# hlw8012_test_board.net
KiCad netlist of a schematic drawn in EAGLE
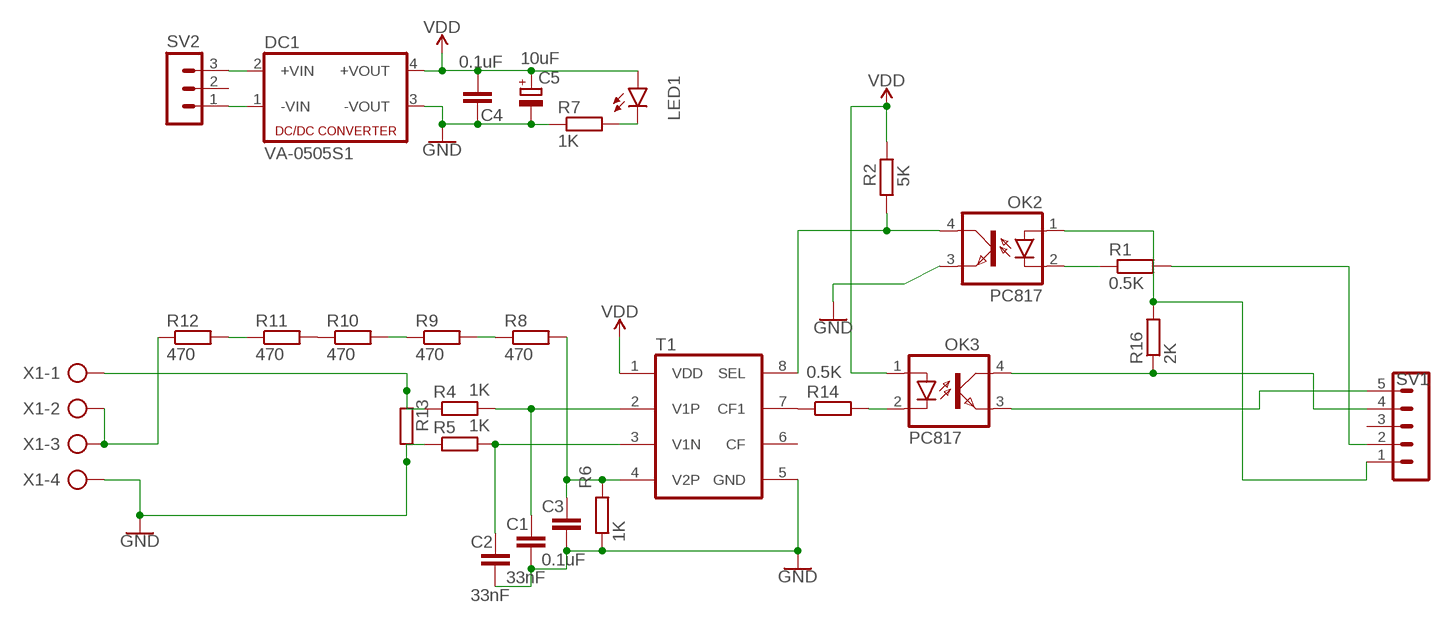
[diagram p0: schematic, sheet 1]

(export (version "E")
  (design (tool "Eeschema 10.0.6"))
  (components
    (comp (ref "C1")
      (value "33nF")
      (footprint "eagle-import:C0805")
      (libsource (lib "eagle-import") (part "C-EUC0805"))
    )
    (comp (ref "C2")
      (value "33nF")
      (footprint "eagle-import:C0805")
      (libsource (lib "eagle-import") (part "C-EUC0805"))
    )
    (comp (ref "C3")
      (value "0.1uF")
      (footprint "eagle-import:C0805")
      (libsource (lib "eagle-import") (part "C-EUC0805"))
    )
    (comp (ref "C4")
      (value "0.1uF")
      (footprint "eagle-import:C0805")
      (libsource (lib "eagle-import") (part "C-EUC0805"))
    )
    (comp (ref "C5")
      (value "10uF")
      (footprint "eagle-import:153CLV-0405")
      (libsource (lib "eagle-import") (part "CPOL-EU153CLV-0405"))
    )
    (comp (ref "DC1")
      (value "VA-0505S1")
      (footprint "eagle-import:4SIL")
      (libsource (lib "eagle-import") (part "VA-?S10505"))
    )
    (comp (ref "LED1")
      (value "LED3MM")
      (footprint "eagle-import:LED3MM")
      (libsource (lib "eagle-import") (part "LED3MM"))
    )
    (comp (ref "OK2")
      (value "PC817")
      (footprint "eagle-import:DIL04")
      (fields (field (name "MPN") "PC817X4J000F"))
      (libsource (lib "eagle-import") (part "PC817"))
    )
    (comp (ref "OK3")
      (value "PC817")
      (footprint "eagle-import:DIL04")
      (fields (field (name "MPN") "PC817X4J000F"))
      (libsource (lib "eagle-import") (part "PC817"))
    )
    (comp (ref "R1")
      (value "0.5K")
      (footprint "eagle-import:M0805")
      (libsource (lib "eagle-import") (part "R-EU_M0805"))
    )
    (comp (ref "R2")
      (value "5K")
      (footprint "eagle-import:M0805")
      (libsource (lib "eagle-import") (part "R-EU_M0805"))
    )
    (comp (ref "R4")
      (value "1K")
      (footprint "eagle-import:M0805")
      (libsource (lib "eagle-import") (part "R-EU_M0805"))
    )
    (comp (ref "R5")
      (value "1K")
      (footprint "eagle-import:M0805")
      (libsource (lib "eagle-import") (part "R-EU_M0805"))
    )
    (comp (ref "R6")
      (value "1K")
      (footprint "eagle-import:M0805")
      (libsource (lib "eagle-import") (part "R-EU_M0805"))
    )
    (comp (ref "R7")
      (value "1K")
      (footprint "eagle-import:M0805")
      (libsource (lib "eagle-import") (part "R-EU_M0805"))
    )
    (comp (ref "R8")
      (value "470")
      (footprint "eagle-import:M0805")
      (libsource (lib "eagle-import") (part "R-EU_M0805"))
    )
    (comp (ref "R9")
      (value "470")
      (footprint "eagle-import:M0805")
      (libsource (lib "eagle-import") (part "R-EU_M0805"))
    )
    (comp (ref "R10")
      (value "470")
      (footprint "eagle-import:M0805")
      (libsource (lib "eagle-import") (part "R-EU_M0805"))
    )
    (comp (ref "R11")
      (value "470")
      (footprint "eagle-import:M0805")
      (libsource (lib "eagle-import") (part "R-EU_M0805"))
    )
    (comp (ref "R12")
      (value "470")
      (footprint "eagle-import:M0805")
      (libsource (lib "eagle-import") (part "R-EU_M0805"))
    )
    (comp (ref "R13")
      (value "PMD")
      (footprint "eagle-import:PMD")
      (libsource (lib "eagle-import") (part "PMD"))
    )
    (comp (ref "R14")
      (value "0.5K")
      (footprint "eagle-import:M0805")
      (libsource (lib "eagle-import") (part "R-EU_M0805"))
    )
    (comp (ref "R16")
      (value "2K")
      (footprint "eagle-import:M0805")
      (libsource (lib "eagle-import") (part "R-EU_M0805"))
    )
    (comp (ref "SV1")
      (value "MA05-1")
      (footprint "eagle-import:MA05-1")
      (libsource (lib "eagle-import") (part "MA05-1"))
    )
    (comp (ref "SV2")
      (value "MA03-1")
      (footprint "eagle-import:MA03-1")
      (libsource (lib "eagle-import") (part "MA03-1"))
    )
    (comp (ref "T1")
      (value "HLW8012")
      (footprint "eagle-import:SO8")
      (libsource (lib "eagle-import") (part "HLW8012"))
    )
    (comp (ref "X1")
      (value "AK300/4")
      (footprint "eagle-import:AK300_4")
      (libsource (lib "eagle-import") (part "AK300/4"))
    )
  )
  (nets
    (net (code "1") (name "GND") (class "Default")
      (node (ref "C1") (pin "2") (pinfunction "2_2") (pintype "passive"))
      (node (ref "C2") (pin "2") (pinfunction "2_2") (pintype "passive"))
      (node (ref "C3") (pin "2") (pinfunction "2_2") (pintype "passive"))
      (node (ref "C4") (pin "1") (pinfunction "1_1") (pintype "passive"))
      (node (ref "C5") (pin "-") (pinfunction "-_-") (pintype "passive"))
      (node (ref "DC1") (pin "3") (pinfunction "-VOUT_3") (pintype "passive"))
      (node (ref "OK2") (pin "3") (pinfunction "EMIT_3") (pintype "passive"))
      (node (ref "R13") (pin "1") (pinfunction "1_1") (pintype "passive"))
      (node (ref "R5") (pin "1") (pinfunction "1_1") (pintype "passive"))
      (node (ref "R6") (pin "1") (pinfunction "1_1") (pintype "passive"))
      (node (ref "R7") (pin "1") (pinfunction "1_1") (pintype "passive"))
      (node (ref "T1") (pin "5") (pinfunction "GND_5") (pintype "power_in"))
      (node (ref "X1") (pin "4") (pinfunction "KL_4") (pintype "passive"))
    )
    (net (code "2") (name "Net-(DC1-+VIN)") (class "Default")
      (node (ref "DC1") (pin "2") (pinfunction "+VIN_2") (pintype "passive"))
      (node (ref "SV2") (pin "3") (pinfunction "3_3") (pintype "passive"))
    )
    (net (code "3") (name "Net-(DC1--VIN)") (class "Default")
      (node (ref "DC1") (pin "1") (pinfunction "-VIN_1") (pintype "passive"))
      (node (ref "SV2") (pin "1") (pinfunction "1_1") (pintype "passive"))
    )
    (net (code "4") (name "Net-(LED1-C)") (class "Default")
      (node (ref "LED1") (pin "K") (pinfunction "C_K") (pintype "passive"))
      (node (ref "R7") (pin "2") (pinfunction "2_2") (pintype "passive"))
    )
    (net (code "5") (name "Net-(OK2-A)") (class "Default")
      (node (ref "OK2") (pin "1") (pinfunction "A_1") (pintype "passive"))
      (node (ref "R16") (pin "2") (pinfunction "2_2") (pintype "passive"))
      (node (ref "SV1") (pin "1") (pinfunction "1_1") (pintype "passive"))
    )
    (net (code "6") (name "Net-(OK2-C)") (class "Default")
      (node (ref "OK2") (pin "2") (pinfunction "C_2") (pintype "passive"))
      (node (ref "R1") (pin "1") (pinfunction "1_1") (pintype "passive"))
    )
    (net (code "7") (name "Net-(OK2-COL)") (class "Default")
      (node (ref "OK2") (pin "4") (pinfunction "COL_4") (pintype "passive"))
      (node (ref "R2") (pin "1") (pinfunction "1_1") (pintype "passive"))
      (node (ref "T1") (pin "8") (pinfunction "SEL_8") (pintype "input"))
    )
    (net (code "8") (name "Net-(OK3-C)") (class "Default")
      (node (ref "OK3") (pin "2") (pinfunction "C_2") (pintype "passive"))
      (node (ref "R14") (pin "2") (pinfunction "2_2") (pintype "passive"))
    )
    (net (code "9") (name "Net-(OK3-COL)") (class "Default")
      (node (ref "OK3") (pin "4") (pinfunction "COL_4") (pintype "passive"))
      (node (ref "R16") (pin "1") (pinfunction "1_1") (pintype "passive"))
      (node (ref "SV1") (pin "4") (pinfunction "4_4") (pintype "passive"))
    )
    (net (code "10") (name "Net-(OK3-EMIT)") (class "Default")
      (node (ref "OK3") (pin "3") (pinfunction "EMIT_3") (pintype "passive"))
      (node (ref "SV1") (pin "5") (pinfunction "5_5") (pintype "passive"))
    )
    (net (code "11") (name "Net-(R1-Pad2)") (class "Default")
      (node (ref "R1") (pin "2") (pinfunction "2_2") (pintype "passive"))
      (node (ref "SV1") (pin "2") (pinfunction "2_2") (pintype "passive"))
    )
    (net (code "12") (name "Net-(R8-Pad1)") (class "Default")
      (node (ref "R8") (pin "1") (pinfunction "1_1") (pintype "passive"))
      (node (ref "R9") (pin "2") (pinfunction "2_2") (pintype "passive"))
    )
    (net (code "13") (name "Net-(R10-Pad1)") (class "Default")
      (node (ref "R10") (pin "1") (pinfunction "1_1") (pintype "passive"))
      (node (ref "R11") (pin "2") (pinfunction "2_2") (pintype "passive"))
    )
    (net (code "14") (name "Net-(R10-Pad2)") (class "Default")
      (node (ref "R10") (pin "2") (pinfunction "2_2") (pintype "passive"))
      (node (ref "R9") (pin "1") (pinfunction "1_1") (pintype "passive"))
    )
    (net (code "15") (name "Net-(R11-Pad1)") (class "Default")
      (node (ref "R11") (pin "1") (pinfunction "1_1") (pintype "passive"))
      (node (ref "R12") (pin "2") (pinfunction "2_2") (pintype "passive"))
    )
    (net (code "16") (name "Net-(T1-CF1)") (class "Default")
      (node (ref "R14") (pin "1") (pinfunction "1_1") (pintype "passive"))
      (node (ref "T1") (pin "7") (pinfunction "CF1_7") (pintype "output"))
    )
    (net (code "17") (name "Net-(T1-V1N)") (class "Default")
      (node (ref "C2") (pin "1") (pinfunction "1_1") (pintype "passive"))
      (node (ref "R5") (pin "2") (pinfunction "2_2") (pintype "passive"))
      (node (ref "T1") (pin "3") (pinfunction "V1N_3") (pintype "input"))
    )
    (net (code "18") (name "Net-(T1-V1P)") (class "Default")
      (node (ref "C1") (pin "1") (pinfunction "1_1") (pintype "passive"))
      (node (ref "R4") (pin "2") (pinfunction "2_2") (pintype "passive"))
      (node (ref "T1") (pin "2") (pinfunction "V1P_2") (pintype "input"))
    )
    (net (code "19") (name "Net-(T1-V2P)") (class "Default")
      (node (ref "C3") (pin "1") (pinfunction "1_1") (pintype "passive"))
      (node (ref "R6") (pin "2") (pinfunction "2_2") (pintype "passive"))
      (node (ref "R8") (pin "2") (pinfunction "2_2") (pintype "passive"))
      (node (ref "T1") (pin "4") (pinfunction "V2P_4") (pintype "input"))
    )
    (net (code "20") (name "Net-(X1A-KL)") (class "Default")
      (node (ref "R13") (pin "2") (pinfunction "2_2") (pintype "passive"))
      (node (ref "R4") (pin "1") (pinfunction "1_1") (pintype "passive"))
      (node (ref "X1") (pin "1") (pinfunction "KL_1") (pintype "passive"))
    )
    (net (code "21") (name "Net-(X1B-KL)") (class "Default")
      (node (ref "R12") (pin "1") (pinfunction "1_1") (pintype "passive"))
      (node (ref "X1") (pin "2") (pinfunction "KL_2") (pintype "passive"))
      (node (ref "X1") (pin "3") (pinfunction "KL_3") (pintype "passive"))
    )
    (net (code "22") (name "VDD") (class "Default")
      (node (ref "C4") (pin "2") (pinfunction "2_2") (pintype "passive"))
      (node (ref "C5") (pin "+") (pinfunction "+_+") (pintype "passive"))
      (node (ref "DC1") (pin "4") (pinfunction "+VOUT_4") (pintype "passive"))
      (node (ref "LED1") (pin "A") (pinfunction "A_A") (pintype "passive"))
      (node (ref "OK3") (pin "1") (pinfunction "A_1") (pintype "passive"))
      (node (ref "R2") (pin "2") (pinfunction "2_2") (pintype "passive"))
      (node (ref "T1") (pin "1") (pinfunction "VDD_1") (pintype "power_in"))
    )
    (net (code "23") (name "unconnected-(SV1-Pad3)") (class "Default")
      (node (ref "SV1") (pin "3") (pinfunction "3_3") (pintype "passive"))
    )
    (net (code "24") (name "unconnected-(SV2-Pad2)") (class "Default")
      (node (ref "SV2") (pin "2") (pinfunction "2_2") (pintype "passive"))
    )
    (net (code "25") (name "unconnected-(T1-CF-Pad6)") (class "Default")
      (node (ref "T1") (pin "6") (pinfunction "CF_6") (pintype "output"))
    )
  )
)
